# CH-THB.net
KiCad netlist of a schematic drawn in EAGLE
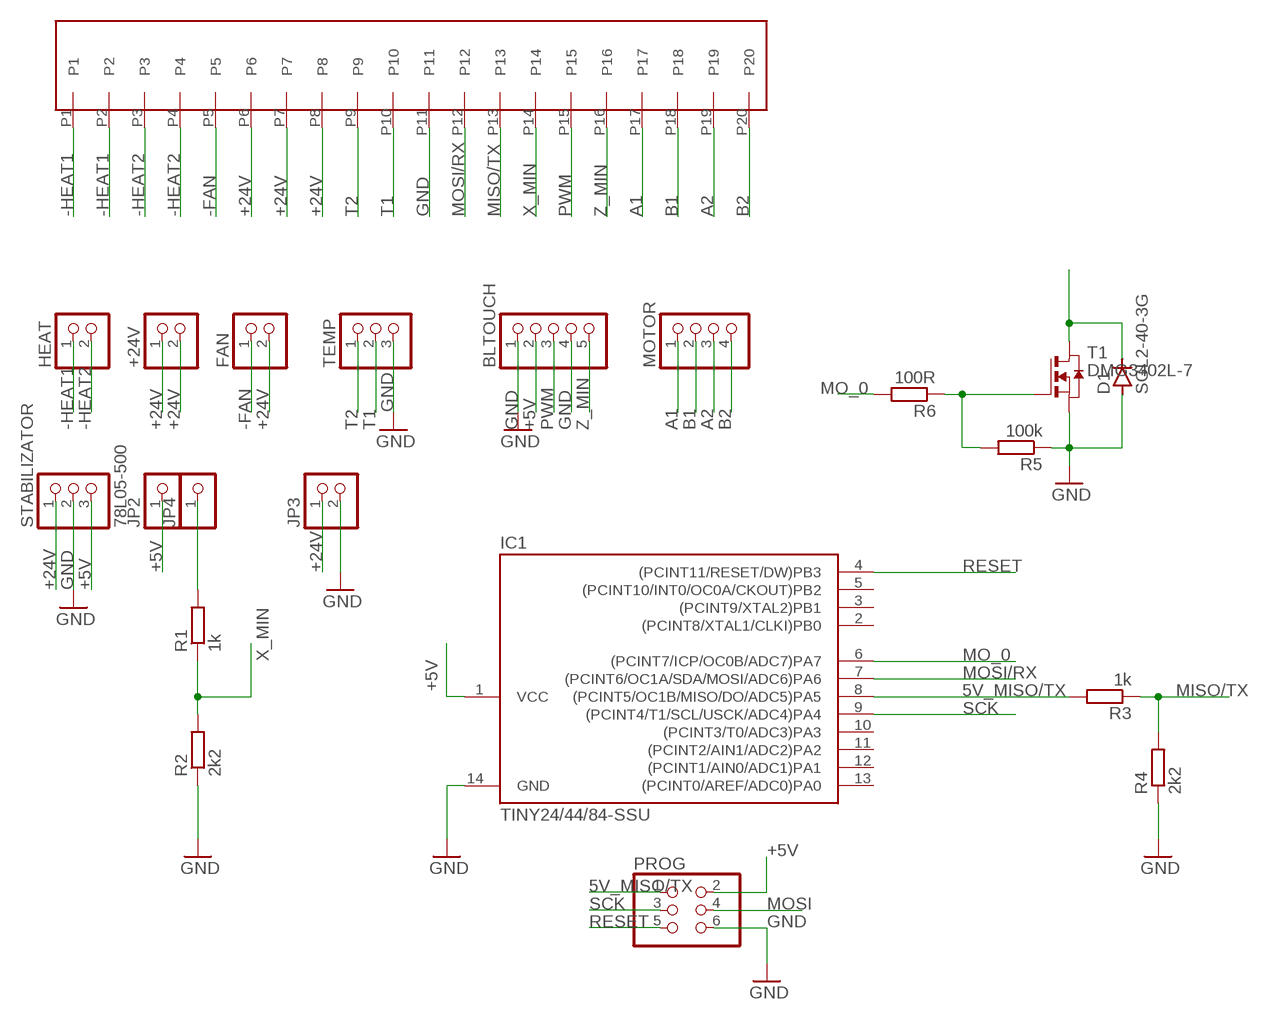
[diagram p0: schematic, sheet 1]

(export (version "E")
  (design (tool "Eeschema 10.0.6"))
  (components
    (comp (ref "+24V")
      (value "PINHD-1X2/LONG")
      (footprint "eagle-import:1X02")
      (libsource (lib "eagle-import") (part "PINHD-1X2/LONG"))
    )
    (comp (ref "BLTOUCH")
      (value "PINHD-1X5/LONG")
      (footprint "eagle-import:1X05")
      (libsource (lib "eagle-import") (part "PINHD-1X5/LONG"))
    )
    (comp (ref "D1")
      (value "SGL2-40-3G")
      (footprint "eagle-import:SOD80")
      (libsource (lib "eagle-import") (part "D-SOD-80"))
    )
    (comp (ref "FAN")
      (value "PINHD-1X2/LONG")
      (footprint "eagle-import:1X02")
      (libsource (lib "eagle-import") (part "PINHD-1X2/LONG"))
    )
    (comp (ref "HEAT")
      (value "PINHD-1X2/LONG")
      (footprint "eagle-import:1X02")
      (libsource (lib "eagle-import") (part "PINHD-1X2/LONG"))
    )
    (comp (ref "IC1")
      (value "TINY24/44/84-SSU")
      (footprint "eagle-import:SOIC14")
      (libsource (lib "eagle-import") (part "TINY24/44/84-SSU"))
    )
    (comp (ref "JP2")
      (value "PINHD-1X1/OCT")
      (footprint "eagle-import:1X01_OCT")
      (libsource (lib "eagle-import") (part "PINHD-1X1/OCT"))
    )
    (comp (ref "JP3")
      (value "PINHD-1X2/OCT")
      (footprint "eagle-import:1X02_OCT")
      (libsource (lib "eagle-import") (part "PINHD-1X2/OCT"))
    )
    (comp (ref "JP4")
      (value "PINHD-1X1/OCT")
      (footprint "eagle-import:1X01_OCT")
      (libsource (lib "eagle-import") (part "PINHD-1X1/OCT"))
    )
    (comp (ref "MOTOR")
      (value "PINHD-1X4/LONG")
      (footprint "eagle-import:1X04")
      (libsource (lib "eagle-import") (part "PINHD-1X4/LONG"))
    )
    (comp (ref "PROG")
      (value "PINHD-2X3/OCT")
      (footprint "eagle-import:2X03")
      (libsource (lib "eagle-import") (part "PINHD-2X3/OCT"))
    )
    (comp (ref "R1")
      (value "1k")
      (footprint "eagle-import:R0603")
      (libsource (lib "eagle-import") (part "R-EU_R0603"))
    )
    (comp (ref "R2")
      (value "2k2")
      (footprint "eagle-import:R0603")
      (libsource (lib "eagle-import") (part "R-EU_R0603"))
    )
    (comp (ref "R3")
      (value "1k")
      (footprint "eagle-import:R0603")
      (libsource (lib "eagle-import") (part "R-EU_R0603"))
    )
    (comp (ref "R4")
      (value "2k2")
      (footprint "eagle-import:R0603")
      (libsource (lib "eagle-import") (part "R-EU_R0603"))
    )
    (comp (ref "R5")
      (value "100k")
      (footprint "eagle-import:R0603")
      (libsource (lib "eagle-import") (part "R-EU_R0603"))
    )
    (comp (ref "R6")
      (value "100R")
      (footprint "eagle-import:R0603")
      (libsource (lib "eagle-import") (part "R-EU_R0603"))
    )
    (comp (ref "STABILIZATOR")
      (value "78L05-500")
      (footprint "eagle-import:1X03_OCT")
      (libsource (lib "eagle-import") (part "PINHD-1X3/OCT"))
    )
    (comp (ref "T1")
      (value "DMG3402L-7")
      (footprint "eagle-import:SOT-23")
      (libsource (lib "eagle-import") (part "NMOSSOT23"))
    )
    (comp (ref "TEMP")
      (value "PINHD-1X3/OCT")
      (footprint "eagle-import:1X03_OCT")
      (libsource (lib "eagle-import") (part "PINHD-1X3/OCT"))
    )
    (comp (ref "U$1")
      (value "PL20")
      (footprint "eagle-import:PL20")
      (libsource (lib "eagle-import") (part "PL20"))
    )
  )
  (nets
    (net (code "1") (name "/+5V") (class "Default")
      (node (ref "BLTOUCH") (pin "2") (pinfunction "2_2") (pintype "passive"))
      (node (ref "IC1") (pin "1") (pinfunction "VCC_1") (pintype "power_in"))
      (node (ref "JP2") (pin "1") (pinfunction "1_1") (pintype "passive"))
      (node (ref "PROG") (pin "2") (pinfunction "2_2") (pintype "passive"))
      (node (ref "STABILIZATOR") (pin "3") (pinfunction "3_3") (pintype "passive"))
    )
    (net (code "2") (name "/+24V") (class "Default")
      (node (ref "+24V") (pin "1") (pinfunction "1_1") (pintype "passive"))
      (node (ref "+24V") (pin "2") (pinfunction "2_2") (pintype "passive"))
      (node (ref "FAN") (pin "2") (pinfunction "2_2") (pintype "passive"))
      (node (ref "JP3") (pin "1") (pinfunction "1_1") (pintype "passive"))
      (node (ref "STABILIZATOR") (pin "1") (pinfunction "1_1") (pintype "passive"))
      (node (ref "U$1") (pin "P6") (pinfunction "P6_P6") (pintype "bidirectional"))
      (node (ref "U$1") (pin "P7") (pinfunction "P7_P7") (pintype "bidirectional"))
      (node (ref "U$1") (pin "P8") (pinfunction "P8_P8") (pintype "bidirectional"))
    )
    (net (code "3") (name "/-FAN") (class "Default")
      (node (ref "FAN") (pin "1") (pinfunction "1_1") (pintype "passive"))
      (node (ref "U$1") (pin "P5") (pinfunction "P5_P5") (pintype "bidirectional"))
    )
    (net (code "4") (name "/-HEAT1") (class "Default")
      (node (ref "HEAT") (pin "1") (pinfunction "1_1") (pintype "passive"))
      (node (ref "U$1") (pin "P1") (pinfunction "P1_P1") (pintype "bidirectional"))
      (node (ref "U$1") (pin "P2") (pinfunction "P2_P2") (pintype "bidirectional"))
    )
    (net (code "5") (name "/-HEAT2") (class "Default")
      (node (ref "HEAT") (pin "2") (pinfunction "2_2") (pintype "passive"))
      (node (ref "U$1") (pin "P3") (pinfunction "P3_P3") (pintype "bidirectional"))
      (node (ref "U$1") (pin "P4") (pinfunction "P4_P4") (pintype "bidirectional"))
    )
    (net (code "6") (name "/5V_MISO{slash}TX") (class "Default")
      (node (ref "IC1") (pin "8") (pinfunction "(PCINT5/OC1B/MISO/DO/ADC5)PA5_8") (pintype "bidirectional"))
      (node (ref "PROG") (pin "1") (pinfunction "1_1") (pintype "passive"))
      (node (ref "R3") (pin "2") (pinfunction "2_2") (pintype "passive"))
    )
    (net (code "7") (name "/A1") (class "Default")
      (node (ref "MOTOR") (pin "1") (pinfunction "1_1") (pintype "passive"))
      (node (ref "U$1") (pin "P17") (pinfunction "P17_P17") (pintype "bidirectional"))
    )
    (net (code "8") (name "/A2") (class "Default")
      (node (ref "MOTOR") (pin "3") (pinfunction "3_3") (pintype "passive"))
      (node (ref "U$1") (pin "P19") (pinfunction "P19_P19") (pintype "bidirectional"))
    )
    (net (code "9") (name "/B1") (class "Default")
      (node (ref "MOTOR") (pin "2") (pinfunction "2_2") (pintype "passive"))
      (node (ref "U$1") (pin "P18") (pinfunction "P18_P18") (pintype "bidirectional"))
    )
    (net (code "10") (name "/B2") (class "Default")
      (node (ref "MOTOR") (pin "4") (pinfunction "4_4") (pintype "passive"))
      (node (ref "U$1") (pin "P20") (pinfunction "P20_P20") (pintype "bidirectional"))
    )
    (net (code "11") (name "/MISO{slash}TX") (class "Default")
      (node (ref "R3") (pin "1") (pinfunction "1_1") (pintype "passive"))
      (node (ref "R4") (pin "2") (pinfunction "2_2") (pintype "passive"))
      (node (ref "U$1") (pin "P13") (pinfunction "P13_P13") (pintype "bidirectional"))
    )
    (net (code "12") (name "/MOSI") (class "Default")
      (node (ref "PROG") (pin "4") (pinfunction "4_4") (pintype "passive"))
    )
    (net (code "13") (name "/MOSI{slash}RX") (class "Default")
      (node (ref "IC1") (pin "7") (pinfunction "(PCINT6/OC1A/SDA/MOSI/ADC6)PA6_7") (pintype "bidirectional"))
      (node (ref "U$1") (pin "P12") (pinfunction "P12_P12") (pintype "bidirectional"))
    )
    (net (code "14") (name "/MO_0") (class "Default")
      (node (ref "IC1") (pin "6") (pinfunction "(PCINT7/ICP/OC0B/ADC7)PA7_6") (pintype "bidirectional"))
      (node (ref "R6") (pin "2") (pinfunction "2_2") (pintype "passive"))
    )
    (net (code "15") (name "/PWM") (class "Default")
      (node (ref "BLTOUCH") (pin "3") (pinfunction "3_3") (pintype "passive"))
      (node (ref "U$1") (pin "P15") (pinfunction "P15_P15") (pintype "bidirectional"))
    )
    (net (code "16") (name "/RESET") (class "Default")
      (node (ref "IC1") (pin "4") (pinfunction "(PCINT11/RESET/DW)PB3_4") (pintype "bidirectional"))
      (node (ref "PROG") (pin "5") (pinfunction "5_5") (pintype "passive"))
    )
    (net (code "17") (name "/SCK") (class "Default")
      (node (ref "IC1") (pin "9") (pinfunction "(PCINT4/T1/SCL/USCK/ADC4)PA4_9") (pintype "bidirectional"))
      (node (ref "PROG") (pin "3") (pinfunction "3_3") (pintype "passive"))
    )
    (net (code "18") (name "/T1") (class "Default")
      (node (ref "TEMP") (pin "2") (pinfunction "2_2") (pintype "passive"))
      (node (ref "U$1") (pin "P10") (pinfunction "P10_P10") (pintype "bidirectional"))
    )
    (net (code "19") (name "/T2") (class "Default")
      (node (ref "TEMP") (pin "1") (pinfunction "1_1") (pintype "passive"))
      (node (ref "U$1") (pin "P9") (pinfunction "P9_P9") (pintype "bidirectional"))
    )
    (net (code "20") (name "/X_MIN") (class "Default")
      (node (ref "R1") (pin "1") (pinfunction "1_1") (pintype "passive"))
      (node (ref "R2") (pin "2") (pinfunction "2_2") (pintype "passive"))
      (node (ref "U$1") (pin "P14") (pinfunction "P14_P14") (pintype "bidirectional"))
    )
    (net (code "21") (name "/Z_MIN") (class "Default")
      (node (ref "BLTOUCH") (pin "5") (pinfunction "5_5") (pintype "passive"))
      (node (ref "U$1") (pin "P16") (pinfunction "P16_P16") (pintype "bidirectional"))
    )
    (net (code "22") (name "GND") (class "Default")
      (node (ref "BLTOUCH") (pin "1") (pinfunction "1_1") (pintype "passive"))
      (node (ref "BLTOUCH") (pin "4") (pinfunction "4_4") (pintype "passive"))
      (node (ref "D1") (pin "2") (pinfunction "A_2") (pintype "passive"))
      (node (ref "IC1") (pin "14") (pinfunction "GND_14") (pintype "power_in"))
      (node (ref "JP3") (pin "2") (pinfunction "2_2") (pintype "passive"))
      (node (ref "PROG") (pin "6") (pinfunction "6_6") (pintype "passive"))
      (node (ref "R2") (pin "1") (pinfunction "1_1") (pintype "passive"))
      (node (ref "R4") (pin "1") (pinfunction "1_1") (pintype "passive"))
      (node (ref "R5") (pin "1") (pinfunction "1_1") (pintype "passive"))
      (node (ref "STABILIZATOR") (pin "2") (pinfunction "2_2") (pintype "passive"))
      (node (ref "T1") (pin "2") (pinfunction "S_2") (pintype "passive"))
      (node (ref "TEMP") (pin "3") (pinfunction "3_3") (pintype "passive"))
      (node (ref "U$1") (pin "P11") (pinfunction "P11_P11") (pintype "bidirectional"))
    )
    (net (code "23") (name "Net-(D1-C)") (class "Default")
      (node (ref "D1") (pin "1") (pinfunction "C_1") (pintype "passive"))
      (node (ref "T1") (pin "1") (pinfunction "D_1") (pintype "passive"))
    )
    (net (code "24") (name "Net-(JP4-Pad1)") (class "Default")
      (node (ref "JP4") (pin "1") (pinfunction "1_1") (pintype "passive"))
      (node (ref "R1") (pin "2") (pinfunction "2_2") (pintype "passive"))
    )
    (net (code "25") (name "Net-(T1-G)") (class "Default")
      (node (ref "R5") (pin "2") (pinfunction "2_2") (pintype "passive"))
      (node (ref "R6") (pin "1") (pinfunction "1_1") (pintype "passive"))
      (node (ref "T1") (pin "3") (pinfunction "G_3") (pintype "passive"))
    )
    (net (code "26") (name "unconnected-(IC1-(PCINT0{slash}AREF{slash}ADC0)PA0-Pad13)") (class "Default")
      (node (ref "IC1") (pin "13") (pinfunction "(PCINT0/AREF/ADC0)PA0_13") (pintype "bidirectional"))
    )
    (net (code "27") (name "unconnected-(IC1-(PCINT1{slash}AIN0{slash}ADC1)PA1-Pad12)") (class "Default")
      (node (ref "IC1") (pin "12") (pinfunction "(PCINT1/AIN0/ADC1)PA1_12") (pintype "bidirectional"))
    )
    (net (code "28") (name "unconnected-(IC1-(PCINT2{slash}AIN1{slash}ADC2)PA2-Pad11)") (class "Default")
      (node (ref "IC1") (pin "11") (pinfunction "(PCINT2/AIN1/ADC2)PA2_11") (pintype "bidirectional"))
    )
    (net (code "29") (name "unconnected-(IC1-(PCINT3{slash}T0{slash}ADC3)PA3-Pad10)") (class "Default")
      (node (ref "IC1") (pin "10") (pinfunction "(PCINT3/T0/ADC3)PA3_10") (pintype "bidirectional"))
    )
    (net (code "30") (name "unconnected-(IC1-(PCINT8{slash}XTAL1{slash}CLKI)PB0-Pad2)") (class "Default")
      (node (ref "IC1") (pin "2") (pinfunction "(PCINT8/XTAL1/CLKI)PB0_2") (pintype "bidirectional"))
    )
    (net (code "31") (name "unconnected-(IC1-(PCINT9{slash}XTAL2)PB1-Pad3)") (class "Default")
      (node (ref "IC1") (pin "3") (pinfunction "(PCINT9/XTAL2)PB1_3") (pintype "bidirectional"))
    )
    (net (code "32") (name "unconnected-(IC1-(PCINT10{slash}INT0{slash}OC0A{slash}CKOUT)PB2-Pad5)") (class "Default")
      (node (ref "IC1") (pin "5") (pinfunction "(PCINT10/INT0/OC0A/CKOUT)PB2_5") (pintype "bidirectional"))
    )
  )
)
